# Tmp102_v10.net
KiCad netlist of a schematic drawn in EAGLE
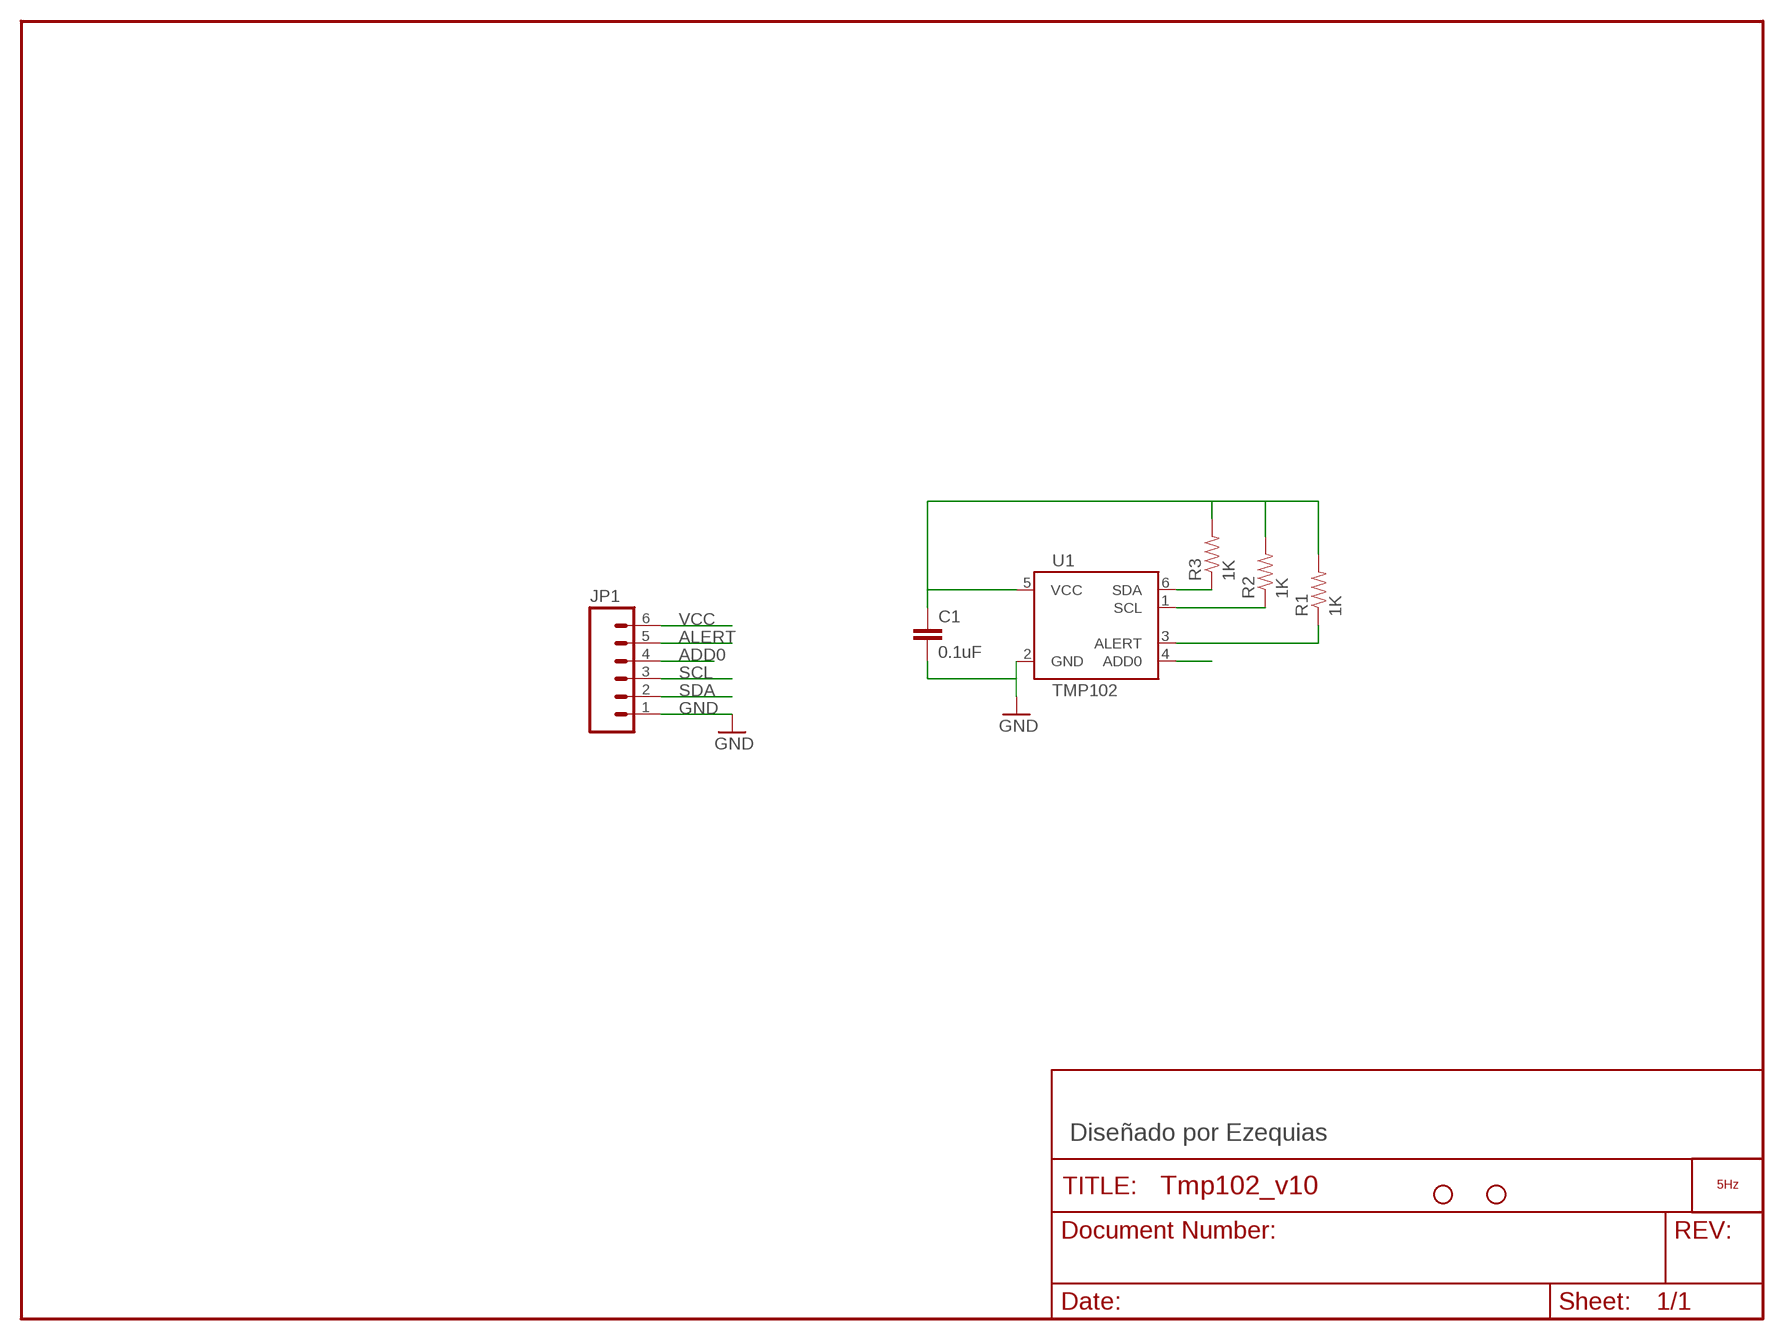
[diagram p0: schematic, sheet 1]

(export (version "E")
  (design (tool "Eeschema 10.0.6"))
  (components
    (comp (ref "C1")
      (value "0.1uF")
      (footprint "eagle-import:0603-CAP")
      (libsource (lib "eagle-import") (part "CAP0603-CAP"))
    )
    (comp (ref "JP1")
      (value "M06SIP")
      (footprint "eagle-import:1X06")
      (libsource (lib "eagle-import") (part "M06SIP"))
    )
    (comp (ref "JP2")
      (value "STAND-OFF")
      (footprint "eagle-import:STAND-OFF")
      (libsource (lib "eagle-import") (part "STAND-OFF"))
    )
    (comp (ref "JP3")
      (value "STAND-OFF")
      (footprint "eagle-import:STAND-OFF")
      (libsource (lib "eagle-import") (part "STAND-OFF"))
    )
    (comp (ref "LOGO1")
      (value "LOGO_5HZ_MAIN_5MM")
      (footprint "eagle-import:5HZ_LOGO_MAIN_5MM")
      (libsource (lib "eagle-import") (part "LOGO_5HZ_MAIN_5MM"))
    )
    (comp (ref "R1")
      (value "1K")
      (footprint "eagle-import:0603-RES")
      (libsource (lib "eagle-import") (part "RESISTOR0603-RES"))
    )
    (comp (ref "R2")
      (value "1K")
      (footprint "eagle-import:0603-RES")
      (libsource (lib "eagle-import") (part "RESISTOR0603-RES"))
    )
    (comp (ref "R3")
      (value "1K")
      (footprint "eagle-import:0603-RES")
      (libsource (lib "eagle-import") (part "RESISTOR0603-RES"))
    )
    (comp (ref "U1")
      (value "TMP102")
      (footprint "eagle-import:SOT563")
      (libsource (lib "eagle-import") (part "TMP102"))
    )
  )
  (nets
    (net (code "1") (name "/ADD0") (class "Default")
      (node (ref "JP1") (pin "4") (pinfunction "4_4") (pintype "passive"))
      (node (ref "U1") (pin "4") (pinfunction "ADD0_4") (pintype "bidirectional"))
    )
    (net (code "2") (name "/ALERT") (class "Default")
      (node (ref "JP1") (pin "5") (pinfunction "5_5") (pintype "passive"))
      (node (ref "R1") (pin "1") (pinfunction "1_1") (pintype "passive"))
      (node (ref "U1") (pin "3") (pinfunction "ALERT_3") (pintype "bidirectional"))
    )
    (net (code "3") (name "/SCL") (class "Default")
      (node (ref "JP1") (pin "3") (pinfunction "3_3") (pintype "passive"))
      (node (ref "R2") (pin "1") (pinfunction "1_1") (pintype "passive"))
      (node (ref "U1") (pin "1") (pinfunction "SCL_1") (pintype "bidirectional"))
    )
    (net (code "4") (name "/SDA") (class "Default")
      (node (ref "JP1") (pin "2") (pinfunction "2_2") (pintype "passive"))
      (node (ref "R3") (pin "1") (pinfunction "1_1") (pintype "passive"))
      (node (ref "U1") (pin "6") (pinfunction "SDA_6") (pintype "bidirectional"))
    )
    (net (code "5") (name "/VCC") (class "Default")
      (node (ref "C1") (pin "1") (pinfunction "1_1") (pintype "passive"))
      (node (ref "JP1") (pin "6") (pinfunction "6_6") (pintype "passive"))
      (node (ref "R1") (pin "2") (pinfunction "2_2") (pintype "passive"))
      (node (ref "R2") (pin "2") (pinfunction "2_2") (pintype "passive"))
      (node (ref "R3") (pin "2") (pinfunction "2_2") (pintype "passive"))
      (node (ref "U1") (pin "5") (pinfunction "VCC_5") (pintype "bidirectional"))
    )
    (net (code "6") (name "GND") (class "Default")
      (node (ref "C1") (pin "2") (pinfunction "2_2") (pintype "passive"))
      (node (ref "JP1") (pin "1") (pinfunction "1_1") (pintype "passive"))
      (node (ref "U1") (pin "2") (pinfunction "GND_2") (pintype "bidirectional"))
    )
  )
)
